# Seeeduino_Mega-shield.net
KiCad netlist of a schematic drawn in EAGLE
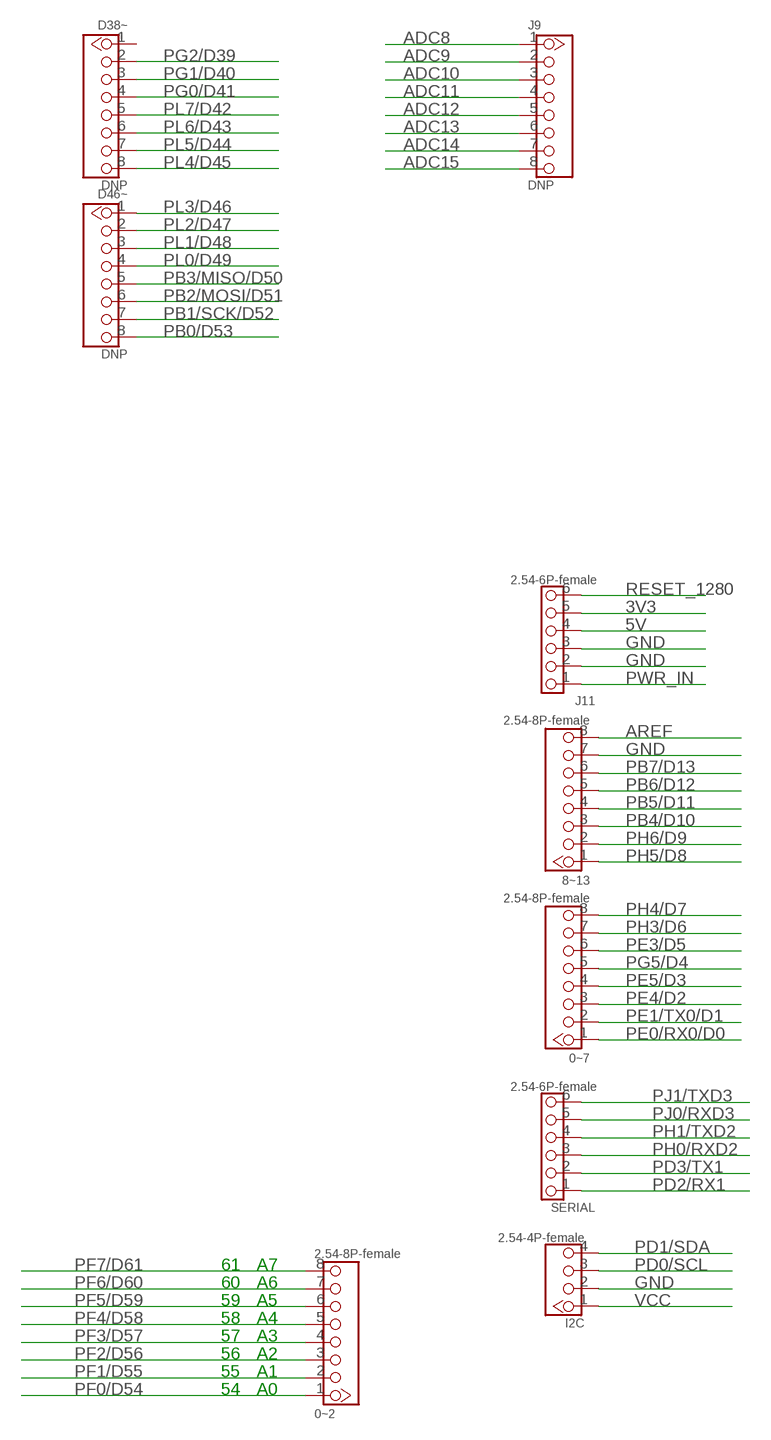
[diagram p0: schematic, sheet 1]

(export (version "E")
  (design (tool "Eeschema 10.0.6"))
  (components
    (comp (ref "0~2")
      (value "2.54-8P-female")
      (footprint "eagle-import:8P-2.54-60_35MIL")
      (libsource (lib "eagle-import") (part "HEADER-8P-60/35MIL"))
    )
    (comp (ref "0~7")
      (value "2.54-8P-female")
      (footprint "eagle-import:8P-2.54-60_35MIL")
      (libsource (lib "eagle-import") (part "HEADER-8P-60/35MIL"))
    )
    (comp (ref "8~13")
      (value "2.54-8P-female")
      (footprint "eagle-import:8P-2.54-60_35MIL")
      (libsource (lib "eagle-import") (part "HEADER-8P-60/35MIL"))
    )
    (comp (ref "D38~")
      (value "DNP")
      (footprint "eagle-import:8P-2.54-60_35MIL")
      (libsource (lib "eagle-import") (part "HEADER-8P-60/35MIL"))
    )
    (comp (ref "D46~")
      (value "DNP")
      (footprint "eagle-import:8P-2.54-60_35MIL")
      (libsource (lib "eagle-import") (part "HEADER-8P-60/35MIL"))
    )
    (comp (ref "I2C")
      (value "2.54-4P-female")
      (footprint "eagle-import:4P-60_35MIL")
      (libsource (lib "eagle-import") (part "HEADER-4P-60/35MIL"))
    )
    (comp (ref "J9")
      (value "DNP")
      (footprint "eagle-import:8P-2.54-60_35MIL")
      (libsource (lib "eagle-import") (part "HEADER-8P-60/35MIL"))
    )
    (comp (ref "J11")
      (value "2.54-6P-female")
      (footprint "eagle-import:6P-2.54-60_35MIL")
      (libsource (lib "eagle-import") (part "HEADER-6P-60/35MIL"))
    )
    (comp (ref "SERIAL")
      (value "2.54-6P-female")
      (footprint "eagle-import:6P-2.54-60_35MIL")
      (libsource (lib "eagle-import") (part "HEADER-6P-60/35MIL"))
    )
  )
  (nets
    (net (code "1") (name "/3V3") (class "Default")
      (node (ref "J11") (pin "5") (pinfunction "5_5") (pintype "bidirectional"))
    )
    (net (code "2") (name "/5V") (class "Default")
      (node (ref "J11") (pin "4") (pinfunction "4_4") (pintype "bidirectional"))
    )
    (net (code "3") (name "/ADC8") (class "Default")
      (node (ref "J9") (pin "1") (pinfunction "1_1") (pintype "bidirectional"))
    )
    (net (code "4") (name "/ADC9") (class "Default")
      (node (ref "J9") (pin "2") (pinfunction "2_2") (pintype "bidirectional"))
    )
    (net (code "5") (name "/ADC10") (class "Default")
      (node (ref "J9") (pin "3") (pinfunction "3_3") (pintype "bidirectional"))
    )
    (net (code "6") (name "/ADC11") (class "Default")
      (node (ref "J9") (pin "4") (pinfunction "4_4") (pintype "bidirectional"))
    )
    (net (code "7") (name "/ADC12") (class "Default")
      (node (ref "J9") (pin "5") (pinfunction "5_5") (pintype "bidirectional"))
    )
    (net (code "8") (name "/ADC13") (class "Default")
      (node (ref "J9") (pin "6") (pinfunction "6_6") (pintype "bidirectional"))
    )
    (net (code "9") (name "/ADC14") (class "Default")
      (node (ref "J9") (pin "7") (pinfunction "7_7") (pintype "bidirectional"))
    )
    (net (code "10") (name "/ADC15") (class "Default")
      (node (ref "J9") (pin "8") (pinfunction "8_8") (pintype "bidirectional"))
    )
    (net (code "11") (name "/AREF") (class "Default")
      (node (ref "8~13") (pin "8") (pinfunction "8_8") (pintype "bidirectional"))
    )
    (net (code "12") (name "/GND") (class "Default")
      (node (ref "8~13") (pin "7") (pinfunction "7_7") (pintype "bidirectional"))
      (node (ref "I2C") (pin "2") (pinfunction "P$2_2") (pintype "bidirectional"))
      (node (ref "J11") (pin "2") (pinfunction "2_2") (pintype "bidirectional"))
      (node (ref "J11") (pin "3") (pinfunction "3_3") (pintype "bidirectional"))
    )
    (net (code "13") (name "/PB0{slash}D53") (class "Default")
      (node (ref "D46~") (pin "8") (pinfunction "8_8") (pintype "bidirectional"))
    )
    (net (code "14") (name "/PB1{slash}SCK{slash}D52") (class "Default")
      (node (ref "D46~") (pin "7") (pinfunction "7_7") (pintype "bidirectional"))
    )
    (net (code "15") (name "/PB2{slash}MOSI{slash}D51") (class "Default")
      (node (ref "D46~") (pin "6") (pinfunction "6_6") (pintype "bidirectional"))
    )
    (net (code "16") (name "/PB3{slash}MISO{slash}D50") (class "Default")
      (node (ref "D46~") (pin "5") (pinfunction "5_5") (pintype "bidirectional"))
    )
    (net (code "17") (name "/PB4{slash}D10") (class "Default")
      (node (ref "8~13") (pin "3") (pinfunction "3_3") (pintype "bidirectional"))
    )
    (net (code "18") (name "/PB5{slash}D11") (class "Default")
      (node (ref "8~13") (pin "4") (pinfunction "4_4") (pintype "bidirectional"))
    )
    (net (code "19") (name "/PB6{slash}D12") (class "Default")
      (node (ref "8~13") (pin "5") (pinfunction "5_5") (pintype "bidirectional"))
    )
    (net (code "20") (name "/PB7{slash}D13") (class "Default")
      (node (ref "8~13") (pin "6") (pinfunction "6_6") (pintype "bidirectional"))
    )
    (net (code "21") (name "/PD0{slash}SCL") (class "Default")
      (node (ref "I2C") (pin "3") (pinfunction "P$3_3") (pintype "bidirectional"))
    )
    (net (code "22") (name "/PD1{slash}SDA") (class "Default")
      (node (ref "I2C") (pin "4") (pinfunction "P$4_4") (pintype "bidirectional"))
    )
    (net (code "23") (name "/PD2{slash}RX1") (class "Default")
      (node (ref "SERIAL") (pin "1") (pinfunction "1_1") (pintype "bidirectional"))
    )
    (net (code "24") (name "/PD3{slash}TX1") (class "Default")
      (node (ref "SERIAL") (pin "2") (pinfunction "2_2") (pintype "bidirectional"))
    )
    (net (code "25") (name "/PE0{slash}RX0{slash}D0") (class "Default")
      (node (ref "0~7") (pin "1") (pinfunction "1_1") (pintype "bidirectional"))
    )
    (net (code "26") (name "/PE1{slash}TX0{slash}D1") (class "Default")
      (node (ref "0~7") (pin "2") (pinfunction "2_2") (pintype "bidirectional"))
    )
    (net (code "27") (name "/PE3{slash}D5") (class "Default")
      (node (ref "0~7") (pin "6") (pinfunction "6_6") (pintype "bidirectional"))
    )
    (net (code "28") (name "/PE4{slash}D2") (class "Default")
      (node (ref "0~7") (pin "3") (pinfunction "3_3") (pintype "bidirectional"))
    )
    (net (code "29") (name "/PE5{slash}D3") (class "Default")
      (node (ref "0~7") (pin "4") (pinfunction "4_4") (pintype "bidirectional"))
    )
    (net (code "30") (name "/PF0{slash}D54") (class "Default")
      (node (ref "0~2") (pin "1") (pinfunction "1_1") (pintype "bidirectional"))
    )
    (net (code "31") (name "/PF1{slash}D55") (class "Default")
      (node (ref "0~2") (pin "2") (pinfunction "2_2") (pintype "bidirectional"))
    )
    (net (code "32") (name "/PF2{slash}D56") (class "Default")
      (node (ref "0~2") (pin "3") (pinfunction "3_3") (pintype "bidirectional"))
    )
    (net (code "33") (name "/PF3{slash}D57") (class "Default")
      (node (ref "0~2") (pin "4") (pinfunction "4_4") (pintype "bidirectional"))
    )
    (net (code "34") (name "/PF4{slash}D58") (class "Default")
      (node (ref "0~2") (pin "5") (pinfunction "5_5") (pintype "bidirectional"))
    )
    (net (code "35") (name "/PF5{slash}D59") (class "Default")
      (node (ref "0~2") (pin "6") (pinfunction "6_6") (pintype "bidirectional"))
    )
    (net (code "36") (name "/PF6{slash}D60") (class "Default")
      (node (ref "0~2") (pin "7") (pinfunction "7_7") (pintype "bidirectional"))
    )
    (net (code "37") (name "/PF7{slash}D61") (class "Default")
      (node (ref "0~2") (pin "8") (pinfunction "8_8") (pintype "bidirectional"))
    )
    (net (code "38") (name "/PG0{slash}D41") (class "Default")
      (node (ref "D38~") (pin "4") (pinfunction "4_4") (pintype "bidirectional"))
    )
    (net (code "39") (name "/PG1{slash}D40") (class "Default")
      (node (ref "D38~") (pin "3") (pinfunction "3_3") (pintype "bidirectional"))
    )
    (net (code "40") (name "/PG2{slash}D39") (class "Default")
      (node (ref "D38~") (pin "2") (pinfunction "2_2") (pintype "bidirectional"))
    )
    (net (code "41") (name "/PG5{slash}D4") (class "Default")
      (node (ref "0~7") (pin "5") (pinfunction "5_5") (pintype "bidirectional"))
    )
    (net (code "42") (name "/PH0{slash}RXD2") (class "Default")
      (node (ref "SERIAL") (pin "3") (pinfunction "3_3") (pintype "bidirectional"))
    )
    (net (code "43") (name "/PH1{slash}TXD2") (class "Default")
      (node (ref "SERIAL") (pin "4") (pinfunction "4_4") (pintype "bidirectional"))
    )
    (net (code "44") (name "/PH3{slash}D6") (class "Default")
      (node (ref "0~7") (pin "7") (pinfunction "7_7") (pintype "bidirectional"))
    )
    (net (code "45") (name "/PH4{slash}D7") (class "Default")
      (node (ref "0~7") (pin "8") (pinfunction "8_8") (pintype "bidirectional"))
    )
    (net (code "46") (name "/PH5{slash}D8") (class "Default")
      (node (ref "8~13") (pin "1") (pinfunction "1_1") (pintype "bidirectional"))
    )
    (net (code "47") (name "/PH6{slash}D9") (class "Default")
      (node (ref "8~13") (pin "2") (pinfunction "2_2") (pintype "bidirectional"))
    )
    (net (code "48") (name "/PJ0{slash}RXD3") (class "Default")
      (node (ref "SERIAL") (pin "5") (pinfunction "5_5") (pintype "bidirectional"))
    )
    (net (code "49") (name "/PJ1{slash}TXD3") (class "Default")
      (node (ref "SERIAL") (pin "6") (pinfunction "6_6") (pintype "bidirectional"))
    )
    (net (code "50") (name "/PL0{slash}D49") (class "Default")
      (node (ref "D46~") (pin "4") (pinfunction "4_4") (pintype "bidirectional"))
    )
    (net (code "51") (name "/PL1{slash}D48") (class "Default")
      (node (ref "D46~") (pin "3") (pinfunction "3_3") (pintype "bidirectional"))
    )
    (net (code "52") (name "/PL2{slash}D47") (class "Default")
      (node (ref "D46~") (pin "2") (pinfunction "2_2") (pintype "bidirectional"))
    )
    (net (code "53") (name "/PL3{slash}D46") (class "Default")
      (node (ref "D46~") (pin "1") (pinfunction "1_1") (pintype "bidirectional"))
    )
    (net (code "54") (name "/PL4{slash}D45") (class "Default")
      (node (ref "D38~") (pin "8") (pinfunction "8_8") (pintype "bidirectional"))
    )
    (net (code "55") (name "/PL5{slash}D44") (class "Default")
      (node (ref "D38~") (pin "7") (pinfunction "7_7") (pintype "bidirectional"))
    )
    (net (code "56") (name "/PL6{slash}D43") (class "Default")
      (node (ref "D38~") (pin "6") (pinfunction "6_6") (pintype "bidirectional"))
    )
    (net (code "57") (name "/PL7{slash}D42") (class "Default")
      (node (ref "D38~") (pin "5") (pinfunction "5_5") (pintype "bidirectional"))
    )
    (net (code "58") (name "/PWR_IN") (class "Default")
      (node (ref "J11") (pin "1") (pinfunction "1_1") (pintype "bidirectional"))
    )
    (net (code "59") (name "/RESET_1280") (class "Default")
      (node (ref "J11") (pin "6") (pinfunction "6_6") (pintype "bidirectional"))
    )
    (net (code "60") (name "/VCC") (class "Default")
      (node (ref "I2C") (pin "1") (pinfunction "P$1_1") (pintype "bidirectional"))
    )
    (net (code "61") (name "unconnected-(D38~-Pad1)") (class "Default")
      (node (ref "D38~") (pin "1") (pinfunction "1_1") (pintype "bidirectional"))
    )
  )
)
